# Power.net
KiCad netlist of a schematic drawn in Altium Designer
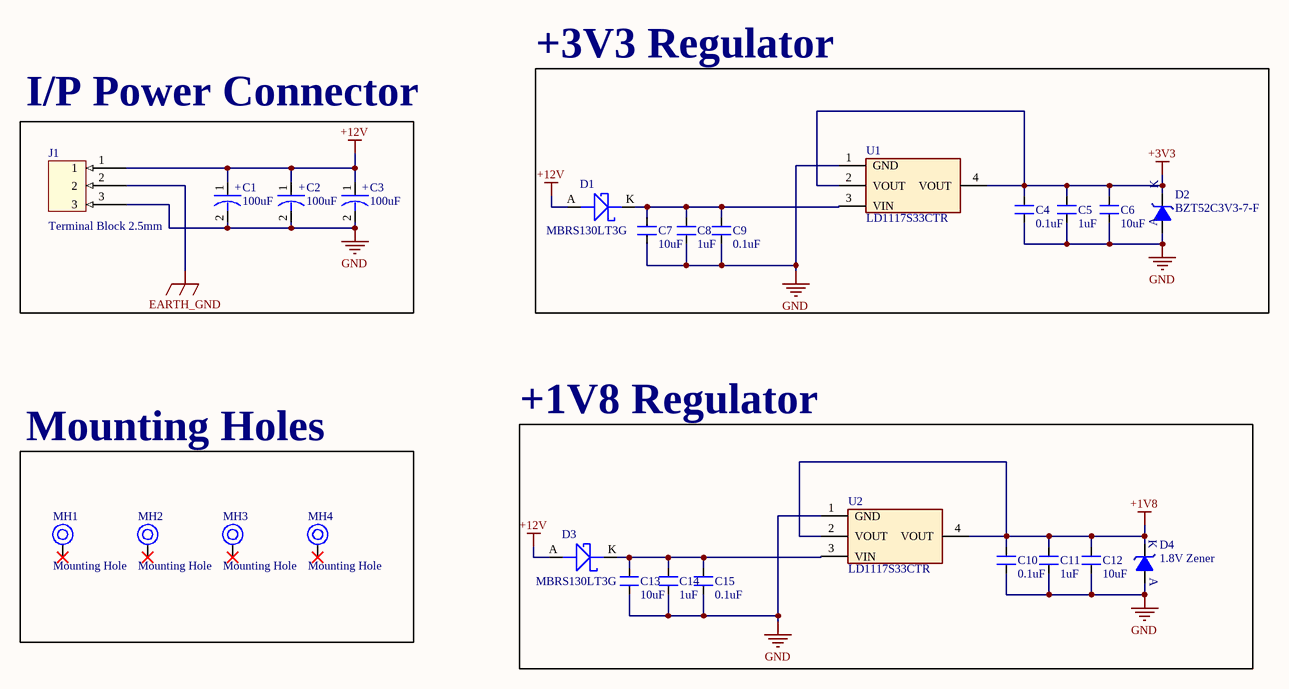
[diagram p0: Power.SchDoc]

(export (version "E")
  (design (tool "Eeschema 10.0.6"))
  (components
    (comp (ref "C1")
      (value "100uF")
      (footprint "ACAP_P305_D393_H393_RAD")
      (description "100µF 50V Aluminum Polymer Capacitor Radial, Can - SMD 28mOhm 4000 Hrs @ 125°C")
      (fields
        (field (name "MANUFACTURER") "Nichicon")
        (field (name "MANUFACTURER PART NUMBER") "GYA1H101MCQ1GS")
      )
      (libsource (lib "STM32F407_Board") (part "CAP-P_100uF-50V-20%-RAD"))
    )
    (comp (ref "C2")
      (value "100uF")
      (footprint "ACAP_P305_D393_H393_RAD")
      (description "100µF 50V Aluminum Polymer Capacitor Radial, Can - SMD 28mOhm 4000 Hrs @ 125°C")
      (fields
        (field (name "MANUFACTURER") "Nichicon")
        (field (name "MANUFACTURER PART NUMBER") "GYA1H101MCQ1GS")
      )
      (libsource (lib "STM32F407_Board") (part "CAP-P_100uF-50V-20%-RAD"))
    )
    (comp (ref "C3")
      (value "100uF")
      (footprint "ACAP_P305_D393_H393_RAD")
      (description "100µF 50V Aluminum Polymer Capacitor Radial, Can - SMD 28mOhm 4000 Hrs @ 125°C")
      (fields
        (field (name "MANUFACTURER") "Nichicon")
        (field (name "MANUFACTURER PART NUMBER") "GYA1H101MCQ1GS")
      )
      (libsource (lib "STM32F407_Board") (part "CAP-P_100uF-50V-20%-RAD"))
    )
    (comp (ref "C4")
      (value "0.1uF")
      (footprint "CAP_0805")
      (description "0.1µF ±10% 50V Ceramic Capacitor X7R 0805 (2012 Metric)")
      (fields
        (field (name "MANUFACTURER") "Samsung")
        (field (name "MANUFACTURER PART NUMBER") "CL21B104KBCNNNC")
      )
      (libsource (lib "STM32F407_Board") (part "CAP_0.1uF-50V-10%-0805"))
    )
    (comp (ref "C5")
      (value "1uF")
      (footprint "CAP_0805")
      (description "1µF ±5% 50V Ceramic Capacitor X7R 0805 (2012 Metric)")
      (fields
        (field (name "MANUFACTURER") "Samsung")
        (field (name "MANUFACTURER PART NUMBER") "CC0805JKX7R9BB105")
      )
      (libsource (lib "STM32F407_Board") (part "CAP_1uF-50V-5%-0805"))
    )
    (comp (ref "C6")
      (value "10uF")
      (footprint "CAP_1206")
      (description "10µF ±10% 50V Ceramic Capacitor X7R 1206 (3216 Metric)")
      (fields
        (field (name "MANUFACTURER") "KEMET")
        (field (name "MANUFACTURER PART NUMBER") "CL31B106KBHNNNE")
      )
      (libsource (lib "STM32F407_Board") (part "CAP_10uF-50V-10%-1206"))
    )
    (comp (ref "C7")
      (value "10uF")
      (footprint "CAP_1206")
      (description "10µF ±10% 50V Ceramic Capacitor X7R 1206 (3216 Metric)")
      (fields
        (field (name "MANUFACTURER") "KEMET")
        (field (name "MANUFACTURER PART NUMBER") "CL31B106KBHNNNE")
      )
      (libsource (lib "STM32F407_Board") (part "CAP_10uF-50V-10%-1206"))
    )
    (comp (ref "C8")
      (value "1uF")
      (footprint "CAP_0805")
      (description "1µF ±5% 50V Ceramic Capacitor X7R 0805 (2012 Metric)")
      (fields
        (field (name "MANUFACTURER") "Samsung")
        (field (name "MANUFACTURER PART NUMBER") "CC0805JKX7R9BB105")
      )
      (libsource (lib "STM32F407_Board") (part "CAP_1uF-50V-5%-0805"))
    )
    (comp (ref "C9")
      (value "0.1uF")
      (footprint "CAP_0805")
      (description "0.1µF ±10% 50V Ceramic Capacitor X7R 0805 (2012 Metric)")
      (fields
        (field (name "MANUFACTURER") "Samsung")
        (field (name "MANUFACTURER PART NUMBER") "CL21B104KBCNNNC")
      )
      (libsource (lib "STM32F407_Board") (part "CAP_0.1uF-50V-10%-0805"))
    )
    (comp (ref "C10")
      (value "0.1uF")
      (footprint "CAP_0805")
      (description "0.1µF ±10% 50V Ceramic Capacitor X7R 0805 (2012 Metric)")
      (fields
        (field (name "MANUFACTURER") "Samsung")
        (field (name "MANUFACTURER PART NUMBER") "CL21B104KBCNNNC")
      )
      (libsource (lib "STM32F407_Board") (part "CAP_0.1uF-50V-10%-0805"))
    )
    (comp (ref "C11")
      (value "1uF")
      (footprint "CAP_0805")
      (description "1µF ±5% 50V Ceramic Capacitor X7R 0805 (2012 Metric)")
      (fields
        (field (name "MANUFACTURER") "Samsung")
        (field (name "MANUFACTURER PART NUMBER") "CC0805JKX7R9BB105")
      )
      (libsource (lib "STM32F407_Board") (part "CAP_1uF-50V-5%-0805"))
    )
    (comp (ref "C12")
      (value "10uF")
      (footprint "CAP_1206")
      (description "10µF ±10% 50V Ceramic Capacitor X7R 1206 (3216 Metric)")
      (fields
        (field (name "MANUFACTURER") "KEMET")
        (field (name "MANUFACTURER PART NUMBER") "CL31B106KBHNNNE")
      )
      (libsource (lib "STM32F407_Board") (part "CAP_10uF-50V-10%-1206"))
    )
    (comp (ref "C13")
      (value "10uF")
      (footprint "CAP_1206")
      (description "10µF ±10% 50V Ceramic Capacitor X7R 1206 (3216 Metric)")
      (fields
        (field (name "MANUFACTURER") "KEMET")
        (field (name "MANUFACTURER PART NUMBER") "CL31B106KBHNNNE")
      )
      (libsource (lib "STM32F407_Board") (part "CAP_10uF-50V-10%-1206"))
    )
    (comp (ref "C14")
      (value "1uF")
      (footprint "CAP_0805")
      (description "1µF ±5% 50V Ceramic Capacitor X7R 0805 (2012 Metric)")
      (fields
        (field (name "MANUFACTURER") "Samsung")
        (field (name "MANUFACTURER PART NUMBER") "CC0805JKX7R9BB105")
      )
      (libsource (lib "STM32F407_Board") (part "CAP_1uF-50V-5%-0805"))
    )
    (comp (ref "C15")
      (value "0.1uF")
      (footprint "CAP_0805")
      (description "0.1µF ±10% 50V Ceramic Capacitor X7R 0805 (2012 Metric)")
      (fields
        (field (name "MANUFACTURER") "Samsung")
        (field (name "MANUFACTURER PART NUMBER") "CL21B104KBCNNNC")
      )
      (libsource (lib "STM32F407_Board") (part "CAP_0.1uF-50V-10%-0805"))
    )
    (comp (ref "D1")
      (value "MBRS130LT3G")
      (footprint "DIO_SMB_DO-214AA")
      (description "Diode Schottky 30V 2A Surface Mount SMB")
      (fields (field (name "MANUFACTURER") "ON Semiconductor"))
      (libsource (lib "STM32F407_Board") (part "DIO-S_445mV-30V-2A-SMB"))
    )
    (comp (ref "D2")
      (value "BZT52C3V3-7-F")
      (footprint "DIO_SOD-123")
      (description "Zener Diode 3.3V 500mW ±6% Surface Mount SOD-123")
      (fields (field (name "MANUFACTURER") "Diodes Incorporated"))
      (libsource (lib "STM32F407_Board") (part "DIO-Z_3.3V-500mW-SOD123"))
    )
    (comp (ref "D3")
      (value "MBRS130LT3G")
      (footprint "DIO_SMB_DO-214AA")
      (description "Diode Schottky 30V 2A Surface Mount SMB")
      (fields (field (name "MANUFACTURER") "ON Semiconductor"))
      (libsource (lib "STM32F407_Board") (part "DIO-S_445mV-30V-2A-SMB"))
    )
    (comp (ref "D4")
      (value "1.8V Zener")
      (footprint "DIO_DO-213AB_SMD")
      (description "Zener Diode 1.8V 500mW ±5% Surface Mount DO-213AA")
      (libsource (lib "STM32F407_Board") (part "DIO-Z_1.8V-500mW-DO213AA"))
    )
    (comp (ref "J1")
      (value "Terminal Block 2.5mm")
      (footprint "CON3_100_TB_TH_ST")
      (description "3 Pins, 1 Row 2.54mm Pitch, straight Connector, male")
      (fields
        (field (name "MANUFACTURER PART NUMBER") "1725669")
        (field (name "MANUFACTURER") "Phoenix Contact")
      )
      (libsource (lib "STM32F407_Board") (part "CON-TB_3X1-100-ST-TH"))
    )
    (comp (ref "MH1")
      (value "Mounting Hole")
      (footprint "MOUNTING")
      (fields (field (name "MANUFACTURER PART NUMBER") "NA"))
      (libsource (lib "STM32F407_Board") (part "MH_3.5H_6D"))
    )
    (comp (ref "MH2")
      (value "Mounting Hole")
      (footprint "MOUNTING")
      (fields (field (name "MANUFACTURER PART NUMBER") "NA"))
      (libsource (lib "STM32F407_Board") (part "MH_3.5H_6D"))
    )
    (comp (ref "MH3")
      (value "Mounting Hole")
      (footprint "MOUNTING")
      (fields (field (name "MANUFACTURER PART NUMBER") "NA"))
      (libsource (lib "STM32F407_Board") (part "MH_3.5H_6D"))
    )
    (comp (ref "MH4")
      (value "Mounting Hole")
      (footprint "MOUNTING")
      (fields (field (name "MANUFACTURER PART NUMBER") "NA"))
      (libsource (lib "STM32F407_Board") (part "MH_3.5H_6D"))
    )
    (comp (ref "U1")
      (value "LD1117S33CTR")
      (footprint "SOT223_3")
      (description "Linear Voltage Regulator IC 1 Output 800mA SOT-223")
      (fields (field (name "MANUFACTURER") "STMicroelectronics"))
      (libsource (lib "STM32F407_Board") (part "REG_15V-3.3V-0.9A-12W-SOT223"))
    )
    (comp (ref "U2")
      (value "LD1117S33CTR")
      (footprint "SOT223_3")
      (description "Linear Voltage Regulator IC 1 Output 800mA SOT-223")
      (fields (field (name "MANUFACTURER") "STMicroelectronics"))
      (libsource (lib "STM32F407_Board") (part "REG_15V-3.3V-0.9A-12W-SOT223"))
    )
  )
  (nets
    (net (code "1") (name "+1V8") (class "Default")
      (node (ref "C10") (pin "2") (pinfunction "2_2") (pintype "passive"))
      (node (ref "C11") (pin "2") (pinfunction "2_2") (pintype "passive"))
      (node (ref "C12") (pin "2") (pinfunction "2_2") (pintype "passive"))
      (node (ref "D4") (pin "K") (pinfunction "K_K") (pintype "passive"))
      (node (ref "U2") (pin "2") (pinfunction "VOUT_2") (pintype "passive"))
      (node (ref "U2") (pin "4") (pinfunction "VOUT_4") (pintype "passive"))
    )
    (net (code "2") (name "+3V3") (class "Default")
      (node (ref "C4") (pin "2") (pinfunction "2_2") (pintype "passive"))
      (node (ref "C5") (pin "2") (pinfunction "2_2") (pintype "passive"))
      (node (ref "C6") (pin "2") (pinfunction "2_2") (pintype "passive"))
      (node (ref "D2") (pin "K") (pinfunction "K_K") (pintype "passive"))
      (node (ref "U1") (pin "2") (pinfunction "VOUT_2") (pintype "passive"))
      (node (ref "U1") (pin "4") (pinfunction "VOUT_4") (pintype "passive"))
    )
    (net (code "3") (name "+12V") (class "Default")
      (node (ref "C1") (pin "1") (pinfunction "1_1") (pintype "passive"))
      (node (ref "C2") (pin "1") (pinfunction "1_1") (pintype "passive"))
      (node (ref "C3") (pin "1") (pinfunction "1_1") (pintype "passive"))
      (node (ref "D1") (pin "A") (pinfunction "A_A") (pintype "passive"))
      (node (ref "D3") (pin "A") (pinfunction "A_A") (pintype "passive"))
      (node (ref "J1") (pin "1") (pinfunction "1_1") (pintype "input"))
    )
    (net (code "4") (name "EARTH_GND") (class "Default")
      (node (ref "J1") (pin "2") (pinfunction "2_2") (pintype "input"))
    )
    (net (code "5") (name "GND") (class "Default")
      (node (ref "C1") (pin "2") (pinfunction "2_2") (pintype "passive"))
      (node (ref "C10") (pin "1") (pinfunction "1_1") (pintype "passive"))
      (node (ref "C11") (pin "1") (pinfunction "1_1") (pintype "passive"))
      (node (ref "C12") (pin "1") (pinfunction "1_1") (pintype "passive"))
      (node (ref "C13") (pin "1") (pinfunction "1_1") (pintype "passive"))
      (node (ref "C14") (pin "1") (pinfunction "1_1") (pintype "passive"))
      (node (ref "C15") (pin "1") (pinfunction "1_1") (pintype "passive"))
      (node (ref "C2") (pin "2") (pinfunction "2_2") (pintype "passive"))
      (node (ref "C3") (pin "2") (pinfunction "2_2") (pintype "passive"))
      (node (ref "C4") (pin "1") (pinfunction "1_1") (pintype "passive"))
      (node (ref "C5") (pin "1") (pinfunction "1_1") (pintype "passive"))
      (node (ref "C6") (pin "1") (pinfunction "1_1") (pintype "passive"))
      (node (ref "C7") (pin "1") (pinfunction "1_1") (pintype "passive"))
      (node (ref "C8") (pin "1") (pinfunction "1_1") (pintype "passive"))
      (node (ref "C9") (pin "1") (pinfunction "1_1") (pintype "passive"))
      (node (ref "D2") (pin "A") (pinfunction "A_A") (pintype "passive"))
      (node (ref "D4") (pin "A") (pinfunction "A_A") (pintype "passive"))
      (node (ref "J1") (pin "3") (pinfunction "3_3") (pintype "input"))
      (node (ref "U1") (pin "1") (pinfunction "GND_1") (pintype "passive"))
      (node (ref "U2") (pin "1") (pinfunction "GND_1") (pintype "passive"))
    )
    (net (code "6") (name "Net-(U1-VIN)") (class "Default")
      (node (ref "C7") (pin "2") (pinfunction "2_2") (pintype "passive"))
      (node (ref "C8") (pin "2") (pinfunction "2_2") (pintype "passive"))
      (node (ref "C9") (pin "2") (pinfunction "2_2") (pintype "passive"))
      (node (ref "D1") (pin "K") (pinfunction "K_K") (pintype "passive"))
      (node (ref "U1") (pin "3") (pinfunction "VIN_3") (pintype "passive"))
    )
    (net (code "7") (name "Net-(U2-VIN)") (class "Default")
      (node (ref "C13") (pin "2") (pinfunction "2_2") (pintype "passive"))
      (node (ref "C14") (pin "2") (pinfunction "2_2") (pintype "passive"))
      (node (ref "C15") (pin "2") (pinfunction "2_2") (pintype "passive"))
      (node (ref "D3") (pin "K") (pinfunction "K_K") (pintype "passive"))
      (node (ref "U2") (pin "3") (pinfunction "VIN_3") (pintype "passive"))
    )
    (net (code "8") (name "unconnected-(MH1-Pad1)") (class "Default")
      (node (ref "MH1") (pin "1") (pinfunction "1_1") (pintype "passive+no_connect"))
    )
    (net (code "9") (name "unconnected-(MH2-Pad1)") (class "Default")
      (node (ref "MH2") (pin "1") (pinfunction "1_1") (pintype "passive+no_connect"))
    )
    (net (code "10") (name "unconnected-(MH3-Pad1)") (class "Default")
      (node (ref "MH3") (pin "1") (pinfunction "1_1") (pintype "passive+no_connect"))
    )
    (net (code "11") (name "unconnected-(MH4-Pad1)") (class "Default")
      (node (ref "MH4") (pin "1") (pinfunction "1_1") (pintype "passive+no_connect"))
    )
  )
)
